# v1.net
KiCad netlist of a schematic drawn in EAGLE
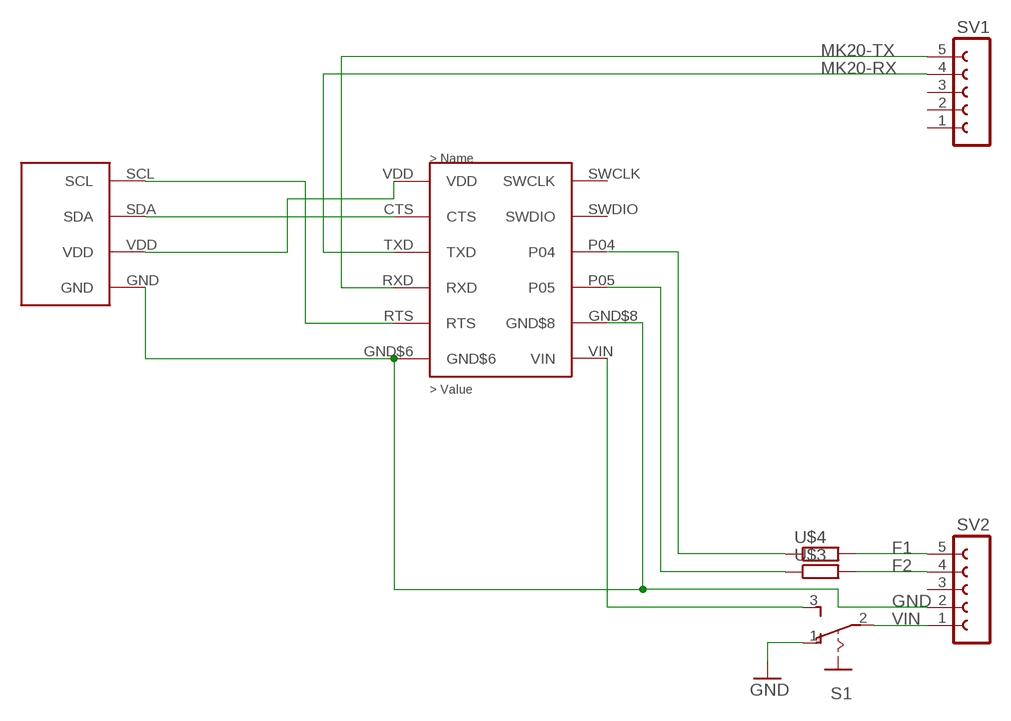
[diagram p0: schematic, sheet 1]

(export (version "E")
  (design (tool "Eeschema 10.0.6"))
  (components
    (comp (ref "9DOF-STICK")
      (value "9D0F-STICK")
      (footprint "eagle-import:9DOF-STICK")
      (libsource (lib "eagle-import") (part "9D0F-STICK"))
    )
    (comp (ref "BLENANO-1.5")
      (value "BLE-NANO-1.5")
      (footprint "eagle-import:BLE-NANO-1.5")
      (libsource (lib "eagle-import") (part "BLE-NANO-1.5"))
    )
    (comp (ref "S1")
      (value "M251")
      (footprint "eagle-import:M251")
      (libsource (lib "eagle-import") (part "M251"))
    )
    (comp (ref "SV1")
      (value "FE05-1")
      (footprint "eagle-import:FE05-1")
      (libsource (lib "eagle-import") (part "FE05-1"))
    )
    (comp (ref "SV2")
      (value "FE05-1")
      (footprint "eagle-import:FE05-1")
      (libsource (lib "eagle-import") (part "FE05-1"))
    )
    (comp (ref "U$3")
      (value "RESISTOR_0201_N")
      (footprint "eagle-import:RESC0201_N")
      (libsource (lib "eagle-import") (part "RESISTOR_0201_N"))
    )
    (comp (ref "U$4")
      (value "RESISTOR_0201_N")
      (footprint "eagle-import:RESC0201_N")
      (libsource (lib "eagle-import") (part "RESISTOR_0201_N"))
    )
  )
  (nets
    (net (code "1") (name "GND") (class "Default")
      (node (ref "S1") (pin "1") (pinfunction "O_1") (pintype "passive"))
    )
    (net (code "2") (name "Net-(9DOF-STICK-PadGND)") (class "Default")
      (node (ref "9DOF-STICK") (pin "GND") (pinfunction "GND_GND") (pintype "bidirectional"))
      (node (ref "BLENANO-1.5") (pin "GND$6") (pinfunction "GND$6_GND$6") (pintype "bidirectional"))
      (node (ref "BLENANO-1.5") (pin "GND$8") (pinfunction "GND$8_GND$8") (pintype "bidirectional"))
      (node (ref "SV2") (pin "2") (pinfunction "2_2") (pintype "passive"))
    )
    (net (code "3") (name "Net-(9DOF-STICK-PadSCL)") (class "Default")
      (node (ref "9DOF-STICK") (pin "SCL") (pinfunction "SCL_SCL") (pintype "bidirectional"))
      (node (ref "BLENANO-1.5") (pin "RTS") (pinfunction "RTS_RTS") (pintype "bidirectional"))
    )
    (net (code "4") (name "Net-(9DOF-STICK-PadSDA)") (class "Default")
      (node (ref "9DOF-STICK") (pin "SDA") (pinfunction "SDA_SDA") (pintype "bidirectional"))
      (node (ref "BLENANO-1.5") (pin "CTS") (pinfunction "CTS_CTS") (pintype "bidirectional"))
    )
    (net (code "5") (name "Net-(9DOF-STICK-PadVDD)") (class "Default")
      (node (ref "9DOF-STICK") (pin "VDD") (pinfunction "VDD_VDD") (pintype "bidirectional"))
      (node (ref "BLENANO-1.5") (pin "VDD") (pinfunction "VDD_VDD") (pintype "bidirectional"))
    )
    (net (code "6") (name "Net-(BLENANO-1.5-PadP04)") (class "Default")
      (node (ref "BLENANO-1.5") (pin "P04") (pinfunction "P04_P04") (pintype "bidirectional"))
      (node (ref "U$4") (pin "1") (pinfunction "1_1") (pintype "passive"))
    )
    (net (code "7") (name "Net-(BLENANO-1.5-PadP05)") (class "Default")
      (node (ref "BLENANO-1.5") (pin "P05") (pinfunction "P05_P05") (pintype "bidirectional"))
      (node (ref "U$3") (pin "1") (pinfunction "1_1") (pintype "passive"))
    )
    (net (code "8") (name "Net-(BLENANO-1.5-PadRXD)") (class "Default")
      (node (ref "BLENANO-1.5") (pin "RXD") (pinfunction "RXD_RXD") (pintype "bidirectional"))
      (node (ref "SV1") (pin "5") (pinfunction "5_5") (pintype "passive"))
    )
    (net (code "9") (name "Net-(BLENANO-1.5-PadTXD)") (class "Default")
      (node (ref "BLENANO-1.5") (pin "TXD") (pinfunction "TXD_TXD") (pintype "bidirectional"))
      (node (ref "SV1") (pin "4") (pinfunction "4_4") (pintype "passive"))
    )
    (net (code "10") (name "Net-(S1-P)") (class "Default")
      (node (ref "S1") (pin "2") (pinfunction "P_2") (pintype "passive"))
      (node (ref "SV2") (pin "1") (pinfunction "1_1") (pintype "passive"))
    )
    (net (code "11") (name "Net-(S1-S)") (class "Default")
      (node (ref "BLENANO-1.5") (pin "VIN") (pinfunction "VIN_VIN") (pintype "bidirectional"))
      (node (ref "S1") (pin "3") (pinfunction "S_3") (pintype "passive"))
    )
    (net (code "12") (name "Net-(SV2-Pad4)") (class "Default")
      (node (ref "SV2") (pin "4") (pinfunction "4_4") (pintype "passive"))
      (node (ref "U$3") (pin "2") (pinfunction "2_2") (pintype "passive"))
    )
    (net (code "13") (name "Net-(SV2-Pad5)") (class "Default")
      (node (ref "SV2") (pin "5") (pinfunction "5_5") (pintype "passive"))
      (node (ref "U$4") (pin "2") (pinfunction "2_2") (pintype "passive"))
    )
    (net (code "14") (name "unconnected-(BLENANO-1.5-PadSWCLK)") (class "Default")
      (node (ref "BLENANO-1.5") (pin "SWCLK") (pinfunction "SWCLK_SWCLK") (pintype "bidirectional"))
    )
    (net (code "15") (name "unconnected-(BLENANO-1.5-PadSWDIO)") (class "Default")
      (node (ref "BLENANO-1.5") (pin "SWDIO") (pinfunction "SWDIO_SWDIO") (pintype "bidirectional"))
    )
    (net (code "16") (name "unconnected-(SV1-Pad1)") (class "Default")
      (node (ref "SV1") (pin "1") (pinfunction "1_1") (pintype "passive"))
    )
    (net (code "17") (name "unconnected-(SV1-Pad2)") (class "Default")
      (node (ref "SV1") (pin "2") (pinfunction "2_2") (pintype "passive"))
    )
    (net (code "18") (name "unconnected-(SV1-Pad3)") (class "Default")
      (node (ref "SV1") (pin "3") (pinfunction "3_3") (pintype "passive"))
    )
    (net (code "19") (name "unconnected-(SV2-Pad3)") (class "Default")
      (node (ref "SV2") (pin "3") (pinfunction "3_3") (pintype "passive"))
    )
  )
)
